# Schematic.net
KiCad netlist of a schematic drawn in EAGLE
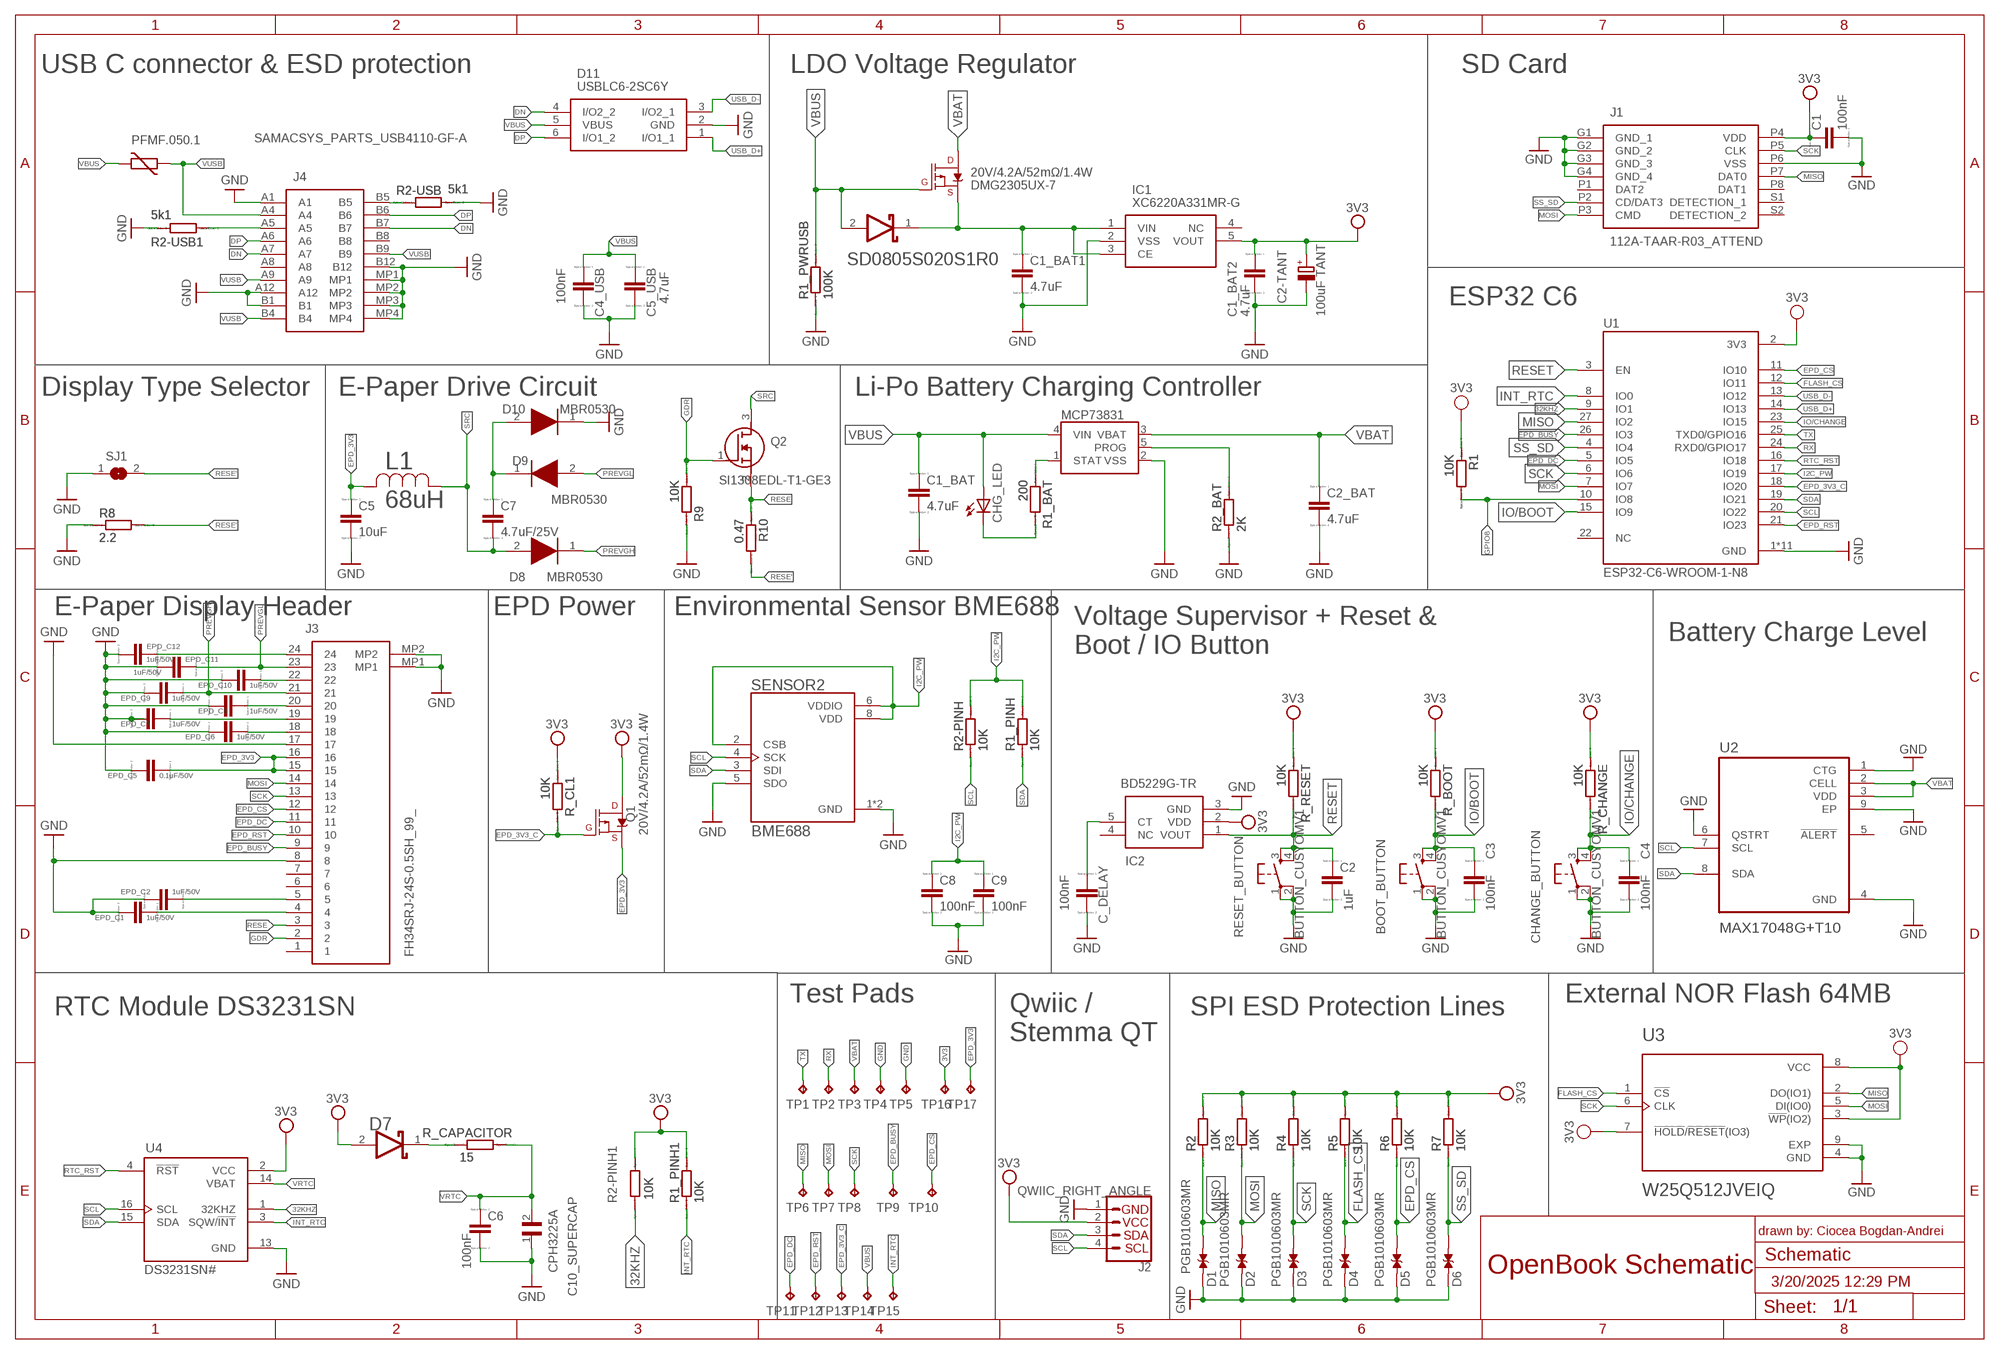
[diagram p0: schematic, sheet 1]

(export (version "E")
  (design (tool "Eeschema 10.0.6"))
  (components
    (comp (ref "BOOT_BUTTON")
      (value "BUTTON_CUSYOMV1")
      (footprint "eagle-import:MYBUTTON")
      (libsource (lib "eagle-import") (part "BUTTON_CUSYOMV1"))
    )
    (comp (ref "C1")
      (value "100nF")
      (footprint "eagle-import:EAGLE-LTSPICE_C0402")
      (libsource (lib "eagle-import") (part "EAGLE-LTSPICE_CC0402"))
    )
    (comp (ref "C1_BAT")
      (value "4.7uF")
      (footprint "eagle-import:EAGLE-LTSPICE_C0402")
      (libsource (lib "eagle-import") (part "EAGLE-LTSPICE_CC0402"))
    )
    (comp (ref "C1_BAT1")
      (value "4.7uF")
      (footprint "eagle-import:EAGLE-LTSPICE_C0402")
      (libsource (lib "eagle-import") (part "EAGLE-LTSPICE_CC0402"))
    )
    (comp (ref "C1_BAT2")
      (value "4.7uF")
      (footprint "eagle-import:EAGLE-LTSPICE_C0402")
      (libsource (lib "eagle-import") (part "EAGLE-LTSPICE_CC0402"))
    )
    (comp (ref "C2")
      (value "1uF")
      (footprint "eagle-import:EAGLE-LTSPICE_C0402")
      (libsource (lib "eagle-import") (part "EAGLE-LTSPICE_CC0402"))
    )
    (comp (ref "C2-TANT")
      (value "100uF TANT")
      (footprint "eagle-import:RCL_CT3528")
      (libsource (lib "eagle-import") (part "RCL_CPOL-EUCT3528"))
    )
    (comp (ref "C2_BAT")
      (value "4.7uF")
      (footprint "eagle-import:EAGLE-LTSPICE_C0402")
      (libsource (lib "eagle-import") (part "EAGLE-LTSPICE_CC0402"))
    )
    (comp (ref "C3")
      (value "100nF")
      (footprint "eagle-import:EAGLE-LTSPICE_C0402")
      (libsource (lib "eagle-import") (part "EAGLE-LTSPICE_CC0402"))
    )
    (comp (ref "C4")
      (value "100nF")
      (footprint "eagle-import:EAGLE-LTSPICE_C0402")
      (libsource (lib "eagle-import") (part "EAGLE-LTSPICE_CC0402"))
    )
    (comp (ref "C4_USB")
      (value "100nF")
      (footprint "eagle-import:EAGLE-LTSPICE_C0402")
      (libsource (lib "eagle-import") (part "EAGLE-LTSPICE_CC0402"))
    )
    (comp (ref "C5")
      (value "10uF")
      (footprint "eagle-import:EAGLE-LTSPICE_C0402")
      (libsource (lib "eagle-import") (part "EAGLE-LTSPICE_CC0402"))
    )
    (comp (ref "C5_USB")
      (value "4.7uF")
      (footprint "eagle-import:EAGLE-LTSPICE_C0402")
      (libsource (lib "eagle-import") (part "EAGLE-LTSPICE_CC0402"))
    )
    (comp (ref "C6")
      (value "100nF")
      (footprint "eagle-import:EAGLE-LTSPICE_C0402")
      (libsource (lib "eagle-import") (part "EAGLE-LTSPICE_CC0402"))
    )
    (comp (ref "C7")
      (value "4.7uF/25V")
      (footprint "eagle-import:EAGLE-LTSPICE_C0402")
      (libsource (lib "eagle-import") (part "EAGLE-LTSPICE_CC0402"))
    )
    (comp (ref "C8")
      (value "100nF")
      (footprint "eagle-import:EAGLE-LTSPICE_C0402")
      (libsource (lib "eagle-import") (part "EAGLE-LTSPICE_CC0402"))
    )
    (comp (ref "C9")
      (value "100nF")
      (footprint "eagle-import:EAGLE-LTSPICE_C0402")
      (libsource (lib "eagle-import") (part "EAGLE-LTSPICE_CC0402"))
    )
    (comp (ref "C10_SUPERCAP")
      (value "CPH3225A")
      (footprint "eagle-import:CAPCP3225X100N")
      (fields (field (name "MF") "Seiko Instruments"))
      (libsource (lib "eagle-import") (part "CPH3225A"))
    )
    (comp (ref "CHANGE_BUTTON")
      (value "BUTTON_CUSYOMV1")
      (footprint "eagle-import:MYBUTTON")
      (libsource (lib "eagle-import") (part "BUTTON_CUSYOMV1"))
    )
    (comp (ref "CHG_LED")
      (value "ADAFRUIT_LEDCHIP-LED0603")
      (footprint "eagle-import:ADAFRUIT_CHIP-LED0603")
      (libsource (lib "eagle-import") (part "ADAFRUIT_LEDCHIP-LED0603"))
    )
    (comp (ref "C_DELAY")
      (value "100nF")
      (footprint "eagle-import:EAGLE-LTSPICE_C0402")
      (libsource (lib "eagle-import") (part "EAGLE-LTSPICE_CC0402"))
    )
    (comp (ref "D1")
      (value "PGB1010603MR")
      (footprint "eagle-import:DIOC1608X36N")
      (fields (field (name "MF") "Littelfuse Inc."))
      (libsource (lib "eagle-import") (part "PGB1010603MR"))
    )
    (comp (ref "D2")
      (value "PGB1010603MR")
      (footprint "eagle-import:DIOC1608X36N")
      (fields (field (name "MF") "Littelfuse Inc."))
      (libsource (lib "eagle-import") (part "PGB1010603MR"))
    )
    (comp (ref "D3")
      (value "PGB1010603MR")
      (footprint "eagle-import:DIOC1608X36N")
      (fields (field (name "MF") "Littelfuse Inc."))
      (libsource (lib "eagle-import") (part "PGB1010603MR"))
    )
    (comp (ref "D4")
      (value "PGB1010603MR")
      (footprint "eagle-import:DIOC1608X36N")
      (fields (field (name "MF") "Littelfuse Inc."))
      (libsource (lib "eagle-import") (part "PGB1010603MR"))
    )
    (comp (ref "D5")
      (value "PGB1010603MR")
      (footprint "eagle-import:DIOC1608X36N")
      (fields (field (name "MF") "Littelfuse Inc."))
      (libsource (lib "eagle-import") (part "PGB1010603MR"))
    )
    (comp (ref "D6")
      (value "PGB1010603MR")
      (footprint "eagle-import:DIOC1608X36N")
      (fields (field (name "MF") "Littelfuse Inc."))
      (libsource (lib "eagle-import") (part "PGB1010603MR"))
    )
    (comp (ref "D7")
      (value "SD0805S020S1R0")
      (footprint "eagle-import:ESP32_WROVER_AVX---SD0805S020S1R0_AVX_SD0805S020S1R0_0")
      (fields
        (field (name "DIGIKEY_PART_NUMBER") "478-7800-1-ND")
        (field (name "MF") "AVX")
        (field (name "MOUSER_PART_NUMBER") "581-SD0805S020S1R0")
      )
      (libsource (lib "eagle-import") (part "ESP32_WROVER_AVX---SD0805S020S1R0_AVX_SD0805S020S1R0_0_0AVX_SD0805S020S1R0_0_0"))
    )
    (comp (ref "D8")
      (value "MBR0530")
      (footprint "eagle-import:SOD3716X135N")
      (fields (field (name "MF") "ON Semiconductor"))
      (libsource (lib "eagle-import") (part "MBR0530"))
    )
    (comp (ref "D9")
      (value "MBR0530")
      (footprint "eagle-import:SOD3716X135N")
      (fields (field (name "MF") "ON Semiconductor"))
      (libsource (lib "eagle-import") (part "MBR0530"))
    )
    (comp (ref "D10")
      (value "MBR0530")
      (footprint "eagle-import:SOD3716X135N")
      (fields (field (name "MF") "ON Semiconductor"))
      (libsource (lib "eagle-import") (part "MBR0530"))
    )
    (comp (ref "D11")
      (value "USBLC6-2SC6Y")
      (footprint "eagle-import:SOT95P280X145-6N")
      (fields (field (name "MF") "STMicroelectronics"))
      (libsource (lib "eagle-import") (part "USBLC6-2SC6Y"))
    )
    (comp (ref "DMG2305UX-7")
      (value "20V/4.2A/52mΩ/1.4W")
      (footprint "eagle-import:ESP32_WROVER_SPARKFUN-DISCRETESEMI_SOT23-3")
      (libsource (lib "eagle-import") (part "ESP32_WROVER_SPARKFUN-DISCRETESEMI_MOSFET_PCH-DMG2305UX-7"))
    )
    (comp (ref "EPD_C1")
      (value "1uF/50V")
      (footprint "eagle-import:EAGLE-LTSPICE_C0402")
      (libsource (lib "eagle-import") (part "EAGLE-LTSPICE_CC0402"))
    )
    (comp (ref "EPD_C2")
      (value "1uF/50V")
      (footprint "eagle-import:EAGLE-LTSPICE_C0402")
      (libsource (lib "eagle-import") (part "EAGLE-LTSPICE_CC0402"))
    )
    (comp (ref "EPD_C5")
      (value "0.1uF/50V")
      (footprint "eagle-import:EAGLE-LTSPICE_C0402")
      (libsource (lib "eagle-import") (part "EAGLE-LTSPICE_CC0402"))
    )
    (comp (ref "EPD_C6")
      (value "1uF/50V")
      (footprint "eagle-import:EAGLE-LTSPICE_C0402")
      (libsource (lib "eagle-import") (part "EAGLE-LTSPICE_CC0402"))
    )
    (comp (ref "EPD_C7")
      (value "1uF/50V")
      (footprint "eagle-import:EAGLE-LTSPICE_C0402")
      (libsource (lib "eagle-import") (part "EAGLE-LTSPICE_CC0402"))
    )
    (comp (ref "EPD_C8")
      (value "1uF/50V")
      (footprint "eagle-import:EAGLE-LTSPICE_C0402")
      (libsource (lib "eagle-import") (part "EAGLE-LTSPICE_CC0402"))
    )
    (comp (ref "EPD_C9")
      (value "1uF/50V")
      (footprint "eagle-import:EAGLE-LTSPICE_C0402")
      (libsource (lib "eagle-import") (part "EAGLE-LTSPICE_CC0402"))
    )
    (comp (ref "EPD_C10")
      (value "1uF/50V")
      (footprint "eagle-import:EAGLE-LTSPICE_C0402")
      (libsource (lib "eagle-import") (part "EAGLE-LTSPICE_CC0402"))
    )
    (comp (ref "EPD_C11")
      (value "1uF/50V")
      (footprint "eagle-import:EAGLE-LTSPICE_C0402")
      (libsource (lib "eagle-import") (part "EAGLE-LTSPICE_CC0402"))
    )
    (comp (ref "EPD_C12")
      (value "1uF/50V")
      (footprint "eagle-import:EAGLE-LTSPICE_C0402")
      (libsource (lib "eagle-import") (part "EAGLE-LTSPICE_CC0402"))
    )
    (comp (ref "IC1")
      (value "XC6220A331MR-G")
      (footprint "eagle-import:SOT95P280X120-5N")
      (fields (field (name "MOUSER_PART_NUMBER") "865-XC6220A331MR-G"))
      (libsource (lib "eagle-import") (part "XC6220A331MR-G"))
    )
    (comp (ref "IC2")
      (value "BD5229G-TR")
      (footprint "eagle-import:SOT95P280X125-5N")
      (fields (field (name "MOUSER_PART_NUMBER") "755-BD5229G-TR"))
      (libsource (lib "eagle-import") (part "BD5229G-TR"))
    )
    (comp (ref "J1")
      (value "112A-TAAR-R03_ATTEND")
      (footprint "eagle-import:112ATAARR03ATTEND")
      (fields (field (name "MANUFACTURER_PART_NUMBER") "112A-TAAR-R03 ATTEND"))
      (libsource (lib "eagle-import") (part "112A-TAAR-R03_ATTEND"))
    )
    (comp (ref "J2")
      (value "QWIIC_RIGHT_ANGLE")
      (footprint "eagle-import:JST04_1MM_RA")
      (libsource (lib "eagle-import") (part "QWIIC_CONNECTORJS-1MM"))
    )
    (comp (ref "J3")
      (value "FH34SRJ-24S-0.5SH_99_")
      (footprint "eagle-import:FH34SRJ24S05SH99")
      (fields
        (field (name "MANUFACTURER_PART_NUMBER") "FH34SRJ-24S-0.5SH(99)")
        (field (name "MOUSER_PART_NUMBER") "798-FH34SRJ24S05SH99")
      )
      (libsource (lib "eagle-import") (part "FH34SRJ-24S-0.5SH_99_"))
    )
    (comp (ref "J4")
      (value "SAMACSYS_PARTS_USB4110-GF-A")
      (footprint "eagle-import:SAMACSYS_PARTS_USB4110GFA")
      (fields
        (field (name "MANUFACTURER_PART_NUMBER") "USB4110-GF-A")
        (field (name "MOUSER_PART_NUMBER") "640-USB4110-GF-A")
      )
      (libsource (lib "eagle-import") (part "SAMACSYS_PARTS_USB4110-GF-A"))
    )
    (comp (ref "L1")
      (value "68uH")
      (footprint "eagle-import:IND_4828-WE-TPC_WRE")
      (fields
        (field (name "MANUFACTURER_PART_NUMBER") "744043680")
        (field (name "COPYRIGHT") "Copyright (C) 2024 Ultra Librarian. All rights reserved.")
      )
      (libsource (lib "eagle-import") (part "744043680IND_4828-WE-TPC_WRE"))
    )
    (comp (ref "MCP73831")
      (value "ESP32_WROVER_SPARKFUN-IC-POWER_MCP73831")
      (footprint "eagle-import:ESP32_WROVER_SPARKFUN-IC-POWER_SOT23-5")
      (libsource (lib "eagle-import") (part "ESP32_WROVER_SPARKFUN-IC-POWER_MCP73831"))
    )
    (comp (ref "PFMF.050.1")
      (value "ESP32C6_VARISTORCN1812")
      (footprint "eagle-import:ESP32C6_VARISTOR_CT_CN1812")
      (libsource (lib "eagle-import") (part "ESP32C6_VARISTORCN1812"))
    )
    (comp (ref "Q1")
      (value "20V/4.2A/52mΩ/1.4W")
      (footprint "eagle-import:ESP32_WROVER_SPARKFUN-DISCRETESEMI_SOT23-3")
      (libsource (lib "eagle-import") (part "ESP32_WROVER_SPARKFUN-DISCRETESEMI_MOSFET_PCH-DMG2305UX-7"))
    )
    (comp (ref "Q2")
      (value "SI1308EDL-T1-GE3")
      (footprint "eagle-import:SOT65P210X110-3N")
      (fields (field (name "MF") "Vishay Siliconix"))
      (libsource (lib "eagle-import") (part "SI1308EDL-T1-GE3"))
    )
    (comp (ref "R1")
      (value "10K")
      (footprint "eagle-import:ESP32_WROVER_EAGLE-LTSPICE_R0402")
      (libsource (lib "eagle-import") (part "ESP32_WROVER_EAGLE-LTSPICE_RR0402"))
    )
    (comp (ref "R1_BAT")
      (value "200")
      (footprint "eagle-import:ESP32_WROVER_EAGLE-LTSPICE_R0402")
      (libsource (lib "eagle-import") (part "ESP32_WROVER_EAGLE-LTSPICE_RR0402"))
    )
    (comp (ref "R1_PINH")
      (value "10K")
      (footprint "eagle-import:ESP32_WROVER_EAGLE-LTSPICE_R0402")
      (libsource (lib "eagle-import") (part "ESP32_WROVER_EAGLE-LTSPICE_RR0402"))
    )
    (comp (ref "R1_PINH1")
      (value "10K")
      (footprint "eagle-import:ESP32_WROVER_EAGLE-LTSPICE_R0402")
      (libsource (lib "eagle-import") (part "ESP32_WROVER_EAGLE-LTSPICE_RR0402"))
    )
    (comp (ref "R1_PWRUSB")
      (value "100K")
      (footprint "eagle-import:ESP32_WROVER_EAGLE-LTSPICE_R0402")
      (libsource (lib "eagle-import") (part "ESP32_WROVER_EAGLE-LTSPICE_RR0402"))
    )
    (comp (ref "R2")
      (value "10K")
      (footprint "eagle-import:ESP32_WROVER_EAGLE-LTSPICE_R0402")
      (libsource (lib "eagle-import") (part "ESP32_WROVER_EAGLE-LTSPICE_RR0402"))
    )
    (comp (ref "R2-PINH")
      (value "10K")
      (footprint "eagle-import:ESP32_WROVER_EAGLE-LTSPICE_R0402")
      (libsource (lib "eagle-import") (part "ESP32_WROVER_EAGLE-LTSPICE_RR0402"))
    )
    (comp (ref "R2-PINH1")
      (value "10K")
      (footprint "eagle-import:ESP32_WROVER_EAGLE-LTSPICE_R0402")
      (libsource (lib "eagle-import") (part "ESP32_WROVER_EAGLE-LTSPICE_RR0402"))
    )
    (comp (ref "R2-USB")
      (value "5k1")
      (footprint "eagle-import:ESP32_WROVER_EAGLE-LTSPICE_R0402")
      (libsource (lib "eagle-import") (part "ESP32_WROVER_EAGLE-LTSPICE_RR0402"))
    )
    (comp (ref "R2-USB1")
      (value "5k1")
      (footprint "eagle-import:ESP32_WROVER_EAGLE-LTSPICE_R0402")
      (libsource (lib "eagle-import") (part "ESP32_WROVER_EAGLE-LTSPICE_RR0402"))
    )
    (comp (ref "R2_BAT")
      (value "2K")
      (footprint "eagle-import:ESP32_WROVER_EAGLE-LTSPICE_R0402")
      (libsource (lib "eagle-import") (part "ESP32_WROVER_EAGLE-LTSPICE_RR0402"))
    )
    (comp (ref "R3")
      (value "10K")
      (footprint "eagle-import:ESP32_WROVER_EAGLE-LTSPICE_R0402")
      (libsource (lib "eagle-import") (part "ESP32_WROVER_EAGLE-LTSPICE_RR0402"))
    )
    (comp (ref "R4")
      (value "10K")
      (footprint "eagle-import:ESP32_WROVER_EAGLE-LTSPICE_R0402")
      (libsource (lib "eagle-import") (part "ESP32_WROVER_EAGLE-LTSPICE_RR0402"))
    )
    (comp (ref "R5")
      (value "10K")
      (footprint "eagle-import:ESP32_WROVER_EAGLE-LTSPICE_R0402")
      (libsource (lib "eagle-import") (part "ESP32_WROVER_EAGLE-LTSPICE_RR0402"))
    )
    (comp (ref "R6")
      (value "10K")
      (footprint "eagle-import:ESP32_WROVER_EAGLE-LTSPICE_R0402")
      (libsource (lib "eagle-import") (part "ESP32_WROVER_EAGLE-LTSPICE_RR0402"))
    )
    (comp (ref "R7")
      (value "10K")
      (footprint "eagle-import:ESP32_WROVER_EAGLE-LTSPICE_R0402")
      (libsource (lib "eagle-import") (part "ESP32_WROVER_EAGLE-LTSPICE_RR0402"))
    )
    (comp (ref "R8")
      (value "2.2")
      (footprint "eagle-import:ESP32_WROVER_EAGLE-LTSPICE_R0402")
      (libsource (lib "eagle-import") (part "ESP32_WROVER_EAGLE-LTSPICE_RR0402"))
    )
    (comp (ref "R9")
      (value "10K")
      (footprint "eagle-import:ESP32_WROVER_EAGLE-LTSPICE_R0402")
      (libsource (lib "eagle-import") (part "ESP32_WROVER_EAGLE-LTSPICE_RR0402"))
    )
    (comp (ref "R10")
      (value "0.47")
      (footprint "eagle-import:ESP32_WROVER_EAGLE-LTSPICE_R0402")
      (libsource (lib "eagle-import") (part "ESP32_WROVER_EAGLE-LTSPICE_RR0402"))
    )
    (comp (ref "RESET_BUTTON")
      (value "BUTTON_CUSYOMV1")
      (footprint "eagle-import:MYBUTTON")
      (libsource (lib "eagle-import") (part "BUTTON_CUSYOMV1"))
    )
    (comp (ref "R_BOOT")
      (value "10K")
      (footprint "eagle-import:ESP32_WROVER_EAGLE-LTSPICE_R0402")
      (libsource (lib "eagle-import") (part "ESP32_WROVER_EAGLE-LTSPICE_RR0402"))
    )
    (comp (ref "R_CAPACITOR")
      (value "15")
      (footprint "eagle-import:ESP32_WROVER_EAGLE-LTSPICE_R0402")
      (libsource (lib "eagle-import") (part "ESP32_WROVER_EAGLE-LTSPICE_RR0402"))
    )
    (comp (ref "R_CHANGE")
      (value "10K")
      (footprint "eagle-import:ESP32_WROVER_EAGLE-LTSPICE_R0402")
      (libsource (lib "eagle-import") (part "ESP32_WROVER_EAGLE-LTSPICE_RR0402"))
    )
    (comp (ref "R_CL1")
      (value "10K")
      (footprint "eagle-import:ESP32_WROVER_EAGLE-LTSPICE_R0402")
      (libsource (lib "eagle-import") (part "ESP32_WROVER_EAGLE-LTSPICE_RR0402"))
    )
    (comp (ref "R_RESET")
      (value "10K")
      (footprint "eagle-import:ESP32_WROVER_EAGLE-LTSPICE_R0402")
      (libsource (lib "eagle-import") (part "ESP32_WROVER_EAGLE-LTSPICE_RR0402"))
    )
    (comp (ref "SD0805S020S1R0")
      (value "ESP32_WROVER_AVX---SD0805S020S1R0_AVX_SD0805S020S1R0_0_0AVX_SD0805S020S1R0_0_0")
      (footprint "eagle-import:ESP32_WROVER_AVX---SD0805S020S1R0_AVX_SD0805S020S1R0_0")
      (fields
        (field (name "DIGIKEY_PART_NUMBER") "478-7800-1-ND")
        (field (name "MF") "AVX")
        (field (name "MOUSER_PART_NUMBER") "581-SD0805S020S1R0")
      )
      (libsource (lib "eagle-import") (part "ESP32_WROVER_AVX---SD0805S020S1R0_AVX_SD0805S020S1R0_0_0AVX_SD0805S020S1R0_0_0"))
    )
    (comp (ref "SENSOR2")
      (value "BME688")
      (footprint "eagle-import:ESP32_WROVER_BME680_PSON80P300X300X100-8N")
      (fields (field (name "MF") "Bosch Sensortec") (field (name "MP") "BME680"))
      (libsource (lib "eagle-import") (part "ESP32_WROVER_BME680_BME680"))
    )
    (comp (ref "SJ1") (value "SJ") (footprint "eagle-import:SJ") (libsource (lib "eagle-import") (part "SJ")))
    (comp (ref "TP1")
      (value "TX")
      (footprint "eagle-import:TP20R")
      (libsource (lib "eagle-import") (part "TPTP20R"))
    )
    (comp (ref "TP2")
      (value "RX")
      (footprint "eagle-import:TP20R")
      (libsource (lib "eagle-import") (part "TPTP20R"))
    )
    (comp (ref "TP3")
      (value "VBAT")
      (footprint "eagle-import:TP20R")
      (libsource (lib "eagle-import") (part "TPTP20R"))
    )
    (comp (ref "TP4")
      (value "GND")
      (footprint "eagle-import:TP20R")
      (libsource (lib "eagle-import") (part "TPTP20R"))
    )
    (comp (ref "TP5")
      (value "GND")
      (footprint "eagle-import:TP20R")
      (libsource (lib "eagle-import") (part "TPTP20R"))
    )
    (comp (ref "TP6")
      (value "MISO")
      (footprint "eagle-import:TP20R")
      (libsource (lib "eagle-import") (part "TPTP20R"))
    )
    (comp (ref "TP7")
      (value "MOSI")
      (footprint "eagle-import:TP20R")
      (libsource (lib "eagle-import") (part "TPTP20R"))
    )
    (comp (ref "TP8")
      (value "SCK")
      (footprint "eagle-import:TP20R")
      (libsource (lib "eagle-import") (part "TPTP20R"))
    )
    (comp (ref "TP9")
      (value "EPD_BUSY")
      (footprint "eagle-import:TP20R")
      (libsource (lib "eagle-import") (part "TPTP20R"))
    )
    (comp (ref "TP10")
      (value "EPD_CS")
      (footprint "eagle-import:TP20R")
      (libsource (lib "eagle-import") (part "TPTP20R"))
    )
    (comp (ref "TP11")
      (value "EPD_DC")
      (footprint "eagle-import:TP20R")
      (libsource (lib "eagle-import") (part "TPTP20R"))
    )
    (comp (ref "TP12")
      (value "EPD_RST")
      (footprint "eagle-import:TP20R")
      (libsource (lib "eagle-import") (part "TPTP20R"))
    )
    (comp (ref "TP13")
      (value "EPD_3V3_C")
      (footprint "eagle-import:TP20R")
      (libsource (lib "eagle-import") (part "TPTP20R"))
    )
    (comp (ref "TP14")
      (value "VBUS")
      (footprint "eagle-import:TP20R")
      (libsource (lib "eagle-import") (part "TPTP20R"))
    )
    (comp (ref "TP15")
      (value "INT_RTC")
      (footprint "eagle-import:TP20R")
      (libsource (lib "eagle-import") (part "TPTP20R"))
    )
    (comp (ref "TP16")
      (value "3V3")
      (footprint "eagle-import:TP20R")
      (libsource (lib "eagle-import") (part "TPTP20R"))
    )
    (comp (ref "TP17")
      (value "EPD_3V3")
      (footprint "eagle-import:TP20R")
      (libsource (lib "eagle-import") (part "TPTP20R"))
    )
    (comp (ref "U1")
      (value "ESP32-C6-WROOM-1-N8")
      (footprint "eagle-import:XCVR_ESP32-C6-WROOM-1-N8")
      (fields (field (name "MF") "Espressif Systems"))
      (libsource (lib "eagle-import") (part "ESP32-C6-WROOM-1-N8"))
    )
    (comp (ref "U2")
      (value "MAX17048G+T10")
      (footprint "eagle-import:SON50P200X200X80-9N")
      (fields (field (name "MF") "Analog Devices"))
      (libsource (lib "eagle-import") (part "MAX17048G+T10"))
    )
    (comp (ref "U3")
      (value "W25Q512JVEIQ")
      (footprint "eagle-import:SON127P600X800X80-9N")
      (fields (field (name "MF") "Winbond Electronics"))
      (libsource (lib "eagle-import") (part "W25Q512JVEIQ"))
    )
    (comp (ref "U4")
      (value "DS3231SN#")
      (footprint "eagle-import:SOIC127P1032X265-16N")
      (fields (field (name "MF") "Analog Devices"))
      (libsource (lib "eagle-import") (part "DS3231SN#"))
    )
  )
  (nets
    (net (code "1") (name "3V3") (class "Default")
      (node (ref "C1") (pin "1") (pinfunction "1_1") (pintype "passive"))
      (node (ref "C1_BAT2") (pin "1") (pinfunction "1_1") (pintype "passive"))
      (node (ref "C2-TANT") (pin "+") (pinfunction "+_+") (pintype "passive"))
      (node (ref "D7") (pin "2") (pinfunction "ANODE_2") (pintype "bidirectional"))
      (node (ref "IC1") (pin "5") (pinfunction "VOUT_5") (pintype "bidirectional"))
      (node (ref "IC2") (pin "2") (pinfunction "VDD_2") (pintype "bidirectional"))
      (node (ref "J1") (pin "P4") (pinfunction "VDD_P4") (pintype "bidirectional"))
      (node (ref "J2") (pin "2") (pinfunction "2_2") (pintype "power_in"))
      (node (ref "Q1") (pin "3") (pinfunction "D_3") (pintype "bidirectional"))
      (node (ref "R1") (pin "1") (pinfunction "1_1") (pintype "passive"))
      (node (ref "R1_PINH1") (pin "2") (pinfunction "2_2") (pintype "passive"))
      (node (ref "R2") (pin "2") (pinfunction "2_2") (pintype "passive"))
      (node (ref "R2-PINH1") (pin "1") (pinfunction "1_1") (pintype "passive"))
      (node (ref "R3") (pin "2") (pinfunction "2_2") (pintype "passive"))
      (node (ref "R4") (pin "2") (pinfunction "2_2") (pintype "passive"))
      (node (ref "R5") (pin "2") (pinfunction "2_2") (pintype "passive"))
      (node (ref "R6") (pin "2") (pinfunction "2_2") (pintype "passive"))
      (node (ref "R7") (pin "2") (pinfunction "2_2") (pintype "passive"))
      (node (ref "R_BOOT") (pin "1") (pinfunction "1_1") (pintype "passive"))
      (node (ref "R_CHANGE") (pin "1") (pinfunction "1_1") (pintype "passive"))
      (node (ref "R_CL1") (pin "1") (pinfunction "1_1") (pintype "passive"))
      (node (ref "R_RESET") (pin "1") (pinfunction "1_1") (pintype "passive"))
      (node (ref "TP16") (pin "TP") (pinfunction "TP_TP") (pintype "input"))
      (node (ref "U1") (pin "2") (pinfunction "3V3_2") (pintype "power_in"))
      (node (ref "U3") (pin "3") (pinfunction "~{WP}(IO2)_3") (pintype "bidirectional"))
      (node (ref "U3") (pin "7") (pinfunction "~{HOLD}/~{RESET}(IO3)_7") (pintype "bidirectional"))
      (node (ref "U3") (pin "8") (pinfunction "VCC_8") (pintype "power_in"))
      (node (ref "U4") (pin "2") (pinfunction "VCC_2") (pintype "power_in"))
    )
    (net (code "2") (name "32KHZ") (class "Default")
      (node (ref "R2-PINH1") (pin "2") (pinfunction "2_2") (pintype "passive"))
      (node (ref "U1") (pin "9") (pinfunction "IO1_9") (pintype "bidirectional"))
      (node (ref "U4") (pin "1") (pinfunction "32KHZ_1") (pintype "output"))
    )
    (net (code "3") (name "DN") (class "Default")
      (node (ref "D11") (pin "4") (pinfunction "I/O2_2_4") (pintype "bidirectional"))
      (node (ref "J4") (pin "A7") (pinfunction "A7_A7") (pintype "bidirectional"))
      (node (ref "J4") (pin "B7") (pinfunction "B7_B7") (pintype "bidirectional"))
    )
    (net (code "4") (name "DP") (class "Default")
      (node (ref "D11") (pin "6") (pinfunction "I/O1_2_6") (pintype "bidirectional"))
      (node (ref "J4") (pin "A6") (pinfunction "A6_A6") (pintype "bidirectional"))
      (node (ref "J4") (pin "B6") (pinfunction "B6_B6") (pintype "bidirectional"))
    )
    (net (code "5") (name "EPD_3V3") (class "Default")
      (node (ref "C5") (pin "1") (pinfunction "1_1") (pintype "passive"))
      (node (ref "EPD_C5") (pin "1") (pinfunction "1_1") (pintype "passive"))
      (node (ref "J3") (pin "15") (pinfunction "15_15") (pintype "bidirectional"))
      (node (ref "J3") (pin "16") (pinfunction "16_16") (pintype "bidirectional"))
      (node (ref "L1") (pin "2") (pinfunction "2_2") (pintype "passive"))
      (node (ref "Q1") (pin "2") (pinfunction "S_2") (pintype "bidirectional"))
      (node (ref "TP17") (pin "TP") (pinfunction "TP_TP") (pintype "input"))
    )
    (net (code "6") (name "EPD_3V3_C") (class "Default")
      (node (ref "Q1") (pin "1") (pinfunction "G_1") (pintype "bidirectional"))
      (node (ref "R_CL1") (pin "2") (pinfunction "2_2") (pintype "passive"))
      (node (ref "TP13") (pin "TP") (pinfunction "TP_TP") (pintype "input"))
      (node (ref "U1") (pin "18") (pinfunction "IO20_18") (pintype "bidirectional"))
    )
    (net (code "7") (name "EPD_BUSY") (class "Default")
      (node (ref "J3") (pin "9") (pinfunction "9_9") (pintype "bidirectional"))
      (node (ref "TP9") (pin "TP") (pinfunction "TP_TP") (pintype "input"))
      (node (ref "U1") (pin "26") (pinfunction "IO3_26") (pintype "bidirectional"))
    )
    (net (code "8") (name "EPD_CS") (class "Default")
      (node (ref "D5") (pin "2") (pinfunction "2_2") (pintype "passive"))
      (node (ref "J3") (pin "12") (pinfunction "12_12") (pintype "bidirectional"))
      (node (ref "R6") (pin "1") (pinfunction "1_1") (pintype "passive"))
      (node (ref "TP10") (pin "TP") (pinfunction "TP_TP") (pintype "input"))
      (node (ref "U1") (pin "11") (pinfunction "IO10_11") (pintype "bidirectional"))
    )
    (net (code "9") (name "EPD_DC") (class "Default")
      (node (ref "J3") (pin "11") (pinfunction "11_11") (pintype "bidirectional"))
      (node (ref "TP11") (pin "TP") (pinfunction "TP_TP") (pintype "input"))
      (node (ref "U1") (pin "5") (pinfunction "IO5_5") (pintype "bidirectional"))
    )
    (net (code "10") (name "EPD_RST") (class "Default")
      (node (ref "J3") (pin "10") (pinfunction "10_10") (pintype "bidirectional"))
      (node (ref "TP12") (pin "TP") (pinfunction "TP_TP") (pintype "input"))
      (node (ref "U1") (pin "21") (pinfunction "IO23_21") (pintype "bidirectional"))
    )
    (net (code "11") (name "FLASH_CS") (class "Default")
      (node (ref "D4") (pin "2") (pinfunction "2_2") (pintype "passive"))
      (node (ref "R5") (pin "1") (pinfunction "1_1") (pintype "passive"))
      (node (ref "U1") (pin "12") (pinfunction "IO11_12") (pintype "bidirectional"))
      (node (ref "U3") (pin "1") (pinfunction "~{CS}_1") (pintype "input"))
    )
    (net (code "12") (name "GDR") (class "Default")
      (node (ref "J3") (pin "2") (pinfunction "2_2") (pintype "bidirectional"))
      (node (ref "Q2") (pin "1") (pinfunction "G_1") (pintype "bidirectional"))
      (node (ref "R9") (pin "1") (pinfunction "1_1") (pintype "passive"))
    )
    (net (code "13") (name "GND") (class "Default")
      (node (ref "BOOT_BUTTON") (pin "1") (pinfunction "1_1") (pintype "passive"))
      (node (ref "BOOT_BUTTON") (pin "2") (pinfunction "2_2") (pintype "passive"))
      (node (ref "C1") (pin "2") (pinfunction "2_2") (pintype "passive"))
      (node (ref "C10_SUPERCAP") (pin "1") (pinfunction "1_1") (pintype "passive"))
      (node (ref "C1_BAT") (pin "2") (pinfunction "2_2") (pintype "passive"))
      (node (ref "C1_BAT1") (pin "2") (pinfunction "2_2") (pintype "passive"))
      (node (ref "C1_BAT2") (pin "2") (pinfunction "2_2") (pintype "passive"))
      (node (ref "C2") (pin "2") (pinfunction "2_2") (pintype "passive"))
      (node (ref "C2-TANT") (pin "-") (pinfunction "-_-") (pintype "passive"))
      (node (ref "C2_BAT") (pin "2") (pinfunction "2_2") (pintype "passive"))
      (node (ref "C3") (pin "2") (pinfunction "2_2") (pintype "passive"))
      (node (ref "C4") (pin "2") (pinfunction "2_2") (pintype "passive"))
      (node (ref "C4_USB") (pin "2") (pinfunction "2_2") (pintype "passive"))
      (node (ref "C5") (pin "2") (pinfunction "2_2") (pintype "passive"))
      (node (ref "C5_USB") (pin "2") (pinfunction "2_2") (pintype "passive"))
      (node (ref "C6") (pin "2") (pinfunction "2_2") (pintype "passive"))
      (node (ref "C8") (pin "2") (pinfunction "2_2") (pintype "passive"))
      (node (ref "C9") (pin "2") (pinfunction "2_2") (pintype "passive"))
      (node (ref "CHANGE_BUTTON") (pin "1") (pinfunction "1_1") (pintype "passive"))
      (node (ref "CHANGE_BUTTON") (pin "2") (pinfunction "2_2") (pintype "passive"))
      (node (ref "C_DELAY") (pin "2") (pinfunction "2_2") (pintype "passive"))
      (node (ref "D1") (pin "1") (pinfunction "1_1") (pintype "passive"))
      (node (ref "D10") (pin "1") (pinfunction "K_1") (pintype "bidirectional"))
      (node (ref "D11") (pin "2") (pinfunction "GND_2") (pintype "bidirectional"))
      (node (ref "D2") (pin "1") (pinfunction "1_1") (pintype "passive"))
      (node (ref "D3") (pin "1") (pinfunction "1_1") (pintype "passive"))
      (node (ref "D4") (pin "1") (pinfunction "1_1") (pintype "passive"))
      (node (ref "D5") (pin "1") (pinfunction "1_1") (pintype "passive"))
      (node (ref "D6") (pin "1") (pinfunction "1_1") (pintype "passive"))
      (node (ref "EPD_C1") (pin "2") (pinfunction "2_2") (pintype "passive"))
      (node (ref "EPD_C10") (pin "2") (pinfunction "2_2") (pintype "passive"))
      (node (ref "EPD_C11") (pin "2") (pinfunction "2_2") (pintype "passive"))
      (node (ref "EPD_C12") (pin "2") (pinfunction "2_2") (pintype "passive"))
      (node (ref "EPD_C2") (pin "2") (pinfunction "2_2") (pintype "passive"))
      (node (ref "EPD_C5") (pin "2") (pinfunction "2_2") (pintype "passive"))
      (node (ref "EPD_C6") (pin "2") (pinfunction "2_2") (pintype "passive"))
      (node (ref "EPD_C7") (pin "2") (pinfunction "2_2") (pintype "passive"))
      (node (ref "EPD_C8") (pin "2") (pinfunction "2_2") (pintype "passive"))
      (node (ref "EPD_C9") (pin "2") (pinfunction "2_2") (pintype "passive"))
      (node (ref "IC1") (pin "2") (pinfunction "VSS_2") (pintype "bidirectional"))
      (node (ref "IC2") (pin "3") (pinfunction "GND_3") (pintype "bidirectional"))
      (node (ref "J1") (pin "G1") (pinfunction "GND_1_G1") (pintype "bidirectional"))
      (node (ref "J1") (pin "G2") (pinfunction "GND_2_G2") (pintype "bidirectional"))
      (node (ref "J1") (pin "G3") (pinfunction "GND_3_G3") (pintype "bidirectional"))
      (node (ref "J1") (pin "G4") (pinfunction "GND_4_G4") (pintype "bidirectional"))
      (node (ref "J1") (pin "P6") (pinfunction "VSS_P6") (pintype "bidirectional"))
      (node (ref "J2") (pin "1") (pinfunction "1_1") (pintype "power_in"))
      (node (ref "J3") (pin "17") (pinfunction "17_17") (pintype "bidirectional"))
      (node (ref "J3") (pin "8") (pinfunction "8_8") (pintype "bidirectional"))
      (node (ref "J3") (pin "MP1") (pinfunction "MP1_MP1") (pintype "bidirectional"))
      (node (ref "J3") (pin "MP2") (pinfunction "MP2_MP2") (pintype "bidirectional"))
      (node (ref "J4") (pin "A1") (pinfunction "A1_A1") (pintype "bidirectional"))
      (node (ref "J4") (pin "A12") (pinfunction "A12_A12") (pintype "bidirectional"))
      (node (ref "J4") (pin "B1") (pinfunction "B1_B1") (pintype "bidirectional"))
      (node (ref "J4") (pin "B12") (pinfunction "B12_B12") (pintype "bidirectional"))
      (node (ref "J4") (pin "MP1") (pinfunction "MP1_MP1") (pintype "bidirectional"))
      (node (ref "J4") (pin "MP2") (pinfunction "MP2_MP2") (pintype "bidirectional"))
      (node (ref "J4") (pin "MP3") (pinfunction "MP3_MP3") (pintype "bidirectional"))
      (node (ref "J4") (pin "MP4") (pinfunction "MP4_MP4") (pintype "bidirectional"))
      (node (ref "MCP73831") (pin "2") (pinfunction "VSS_2") (pintype "power_in"))
      (node (ref "R1_PWRUSB") (pin "1") (pinfunction "1_1") (pintype "passive"))
      (node (ref "R2-USB") (pin "2") (pinfunction "2_2") (pintype "passive"))
      (node (ref "R2-USB1") (pin "1") (pinfunction "1_1") (pintype "passive"))
      (node (ref "R2_BAT") (pin "1") (pinfunction "1_1") (pintype "passive"))
      (node (ref "R8") (pin "1") (pinfunction "1_1") (pintype "passive"))
      (node (ref "R9") (pin "2") (pinfunction "2_2") (pintype "passive"))
      (node (ref "RESET_BUTTON") (pin "1") (pinfunction "1_1") (pintype "passive"))
      (node (ref "RESET_BUTTON") (pin "2") (pinfunction "2_2") (pintype "passive"))
      (node (ref "SENSOR2") (pin "1") (pinfunction "GND_1") (pintype "power_in"))
      (node (ref "SENSOR2") (pin "5") (pinfunction "SDO_5") (pintype "bidirectional"))
      (node (ref "SENSOR2") (pin "7") (pinfunction "GND_7") (pintype "power_in"))
      (node (ref "SJ1") (pin "1") (pinfunction "1_1") (pintype "passive"))
      (node (ref "TP4") (pin "TP") (pinfunction "TP_TP") (pintype "input"))
      (node (ref "TP5") (pin "TP") (pinfunction "TP_TP") (pintype "input"))
      (node (ref "U1") (pin "1") (pinfunction "GND_1") (pintype "power_in"))
      (node (ref "U1") (pin "28") (pinfunction "GND_28") (pintype "power_in"))
      (node (ref "U1") (pin "29_1") (pinfunction "GND_29_1") (pintype "power_in"))
      (node (ref "U1") (pin "29_2") (pinfunction "GND_29_2") (pintype "power_in"))
      (node (ref "U1") (pin "29_3") (pinfunction "GND_29_3") (pintype "power_in"))
      (node (ref "U1") (pin "29_4") (pinfunction "GND_29_4") (pintype "power_in"))
      (node (ref "U1") (pin "29_5") (pinfunction "GND_29_5") (pintype "power_in"))
      (node (ref "U1") (pin "29_6") (pinfunction "GND_29_6") (pintype "power_in"))
      (node (ref "U1") (pin "29_7") (pinfunction "GND_29_7") (pintype "power_in"))
      (node (ref "U1") (pin "29_8") (pinfunction "GND_29_8") (pintype "power_in"))
      (node (ref "U1") (pin "29_9") (pinfunction "GND_29_9") (pintype "power_in"))
      (node (ref "U2") (pin "1") (pinfunction "CTG_1") (pintype "power_in"))
      (node (ref "U2") (pin "4") (pinfunction "GND_4") (pintype "power_in"))
      (node (ref "U2") (pin "6") (pinfunction "QSTRT_6") (pintype "input"))
      (node (ref "U2") (pin "9") (pinfunction "EP_9") (pintype "power_in"))
      (node (ref "U3") (pin "4") (pinfunction "GND_4") (pintype "power_in"))
      (node (ref "U3") (pin "9") (pinfunction "EXP_9") (pintype "passive"))
      (node (ref "U4") (pin "13") (pinfunction "GND_13") (pintype "power_in"))
    )
    (net (code "14") (name "GPIO8") (class "Default")
      (node (ref "R1") (pin "2") (pinfunction "2_2") (pintype "passive"))
      (node (ref "U1") (pin "10") (pinfunction "IO8_10") (pintype "bidirectional"))
    )
    (net (code "15") (name "I2C_PW") (class "Default")
      (node (ref "C8") (pin "1") (pinfunction "1_1") (pintype "passive"))
      (node (ref "C9") (pin "1") (pinfunction "1_1") (pintype "passive"))
      (node (ref "R1_PINH") (pin "2") (pinfunction "2_2") (pintype "passive"))
      (node (ref "R2-PINH") (pin "2") (pinfunction "2_2") (pintype "passive"))
      (node (ref "SENSOR2") (pin "2") (pinfunction "CSB_2") (pintype "input"))
      (node (ref "SENSOR2") (pin "6") (pinfunction "VDDIO_6") (pintype "power_in"))
      (node (ref "SENSOR2") (pin "8") (pinfunction "VDD_8") (pintype "power_in"))
      (node (ref "U1") (pin "17") (pinfunction "IO19_17") (pintype "bidirectional"))
    )
    (net (code "16") (name "INT_RTC") (class "Default")
      (node (ref "R1_PINH1") (pin "1") (pinfunction "1_1") (pintype "passive"))
      (node (ref "TP15") (pin "TP") (pinfunction "TP_TP") (pintype "input"))
      (node (ref "U1") (pin "8") (pinfunction "IO0_8") (pintype "bidirectional"))
      (node (ref "U4") (pin "3") (pinfunction "SQW/~{INT}_3") (pintype "output"))
    )
    (net (code "17") (name "IO{slash}BOOT") (class "Default")
      (node (ref "BOOT_BUTTON") (pin "3") (pinfunction "3_3") (pintype "passive"))
      (node (ref "BOOT_BUTTON") (pin "4") (pinfunction "4_4") (pintype "passive"))
      (node (ref "C3") (pin "1") (pinfunction "1_1") (pintype "passive"))
      (node (ref "R_BOOT") (pin "2") (pinfunction "2_2") (pintype "passive"))
      (node (ref "U1") (pin "15") (pinfunction "IO9_15") (pintype "bidirectional"))
    )
    (net (code "18") (name "IO{slash}CHANGE") (class "Default")
      (node (ref "C4") (pin "1") (pinfunction "1_1") (pintype "passive"))
      (node (ref "CHANGE_BUTTON") (pin "3") (pinfunction "3_3") (pintype "passive"))
      (node (ref "CHANGE_BUTTON") (pin "4") (pinfunction "4_4") (pintype "passive"))
      (node (ref "R_CHANGE") (pin "2") (pinfunction "2_2") (pintype "passive"))
      (node (ref "U1") (pin "23") (pinfunction "IO15_23") (pintype "bidirectional"))
    )
    (net (code "19") (name "MISO") (class "Default")
      (node (ref "D1") (pin "2") (pinfunction "2_2") (pintype "passive"))
      (node (ref "J1") (pin "P7") (pinfunction "DAT0_P7") (pintype "bidirectional"))
      (node (ref "R2") (pin "1") (pinfunction "1_1") (pintype "passive"))
      (node (ref "TP6") (pin "TP") (pinfunction "TP_TP") (pintype "input"))
      (node (ref "U1") (pin "27") (pinfunction "IO2_27") (pintype "bidirectional"))
      (node (ref "U3") (pin "2") (pinfunction "DO(IO1)_2") (pintype "bidirectional"))
    )
    (net (code "20") (name "MOSI") (class "Default")
      (node (ref "D2") (pin "2") (pinfunction "2_2") (pintype "passive"))
      (node (ref "J1") (pin "P3") (pinfunction "CMD_P3") (pintype "bidirectional"))
      (node (ref "J3") (pin "14") (pinfunction "14_14") (pintype "bidirectional"))
      (node (ref "R3") (pin "1") (pinfunction "1_1") (pintype "passive"))
      (node (ref "TP7") (pin "TP") (pinfunction "TP_TP") (pintype "input"))
      (node (ref "U1") (pin "7") (pinfunction "IO7_7") (pintype "bidirectional"))
      (node (ref "U3") (pin "5") (pinfunction "DI(IO0)_5") (pintype "bidirectional"))
    )
    (net (code "21") (name "Net-(CHG_LED-PadC)") (class "Default")
      (node (ref "CHG_LED") (pin "C") (pinfunction "C_C") (pintype "passive"))
      (node (ref "R1_BAT") (pin "2") (pinfunction "2_2") (pintype "passive"))
    )
    (net (code "22") (name "Net-(D7-CATHODE)") (class "Default")
      (node (ref "D7") (pin "1") (pinfunction "CATHODE_1") (pintype "bidirectional"))
      (node (ref "R_CAPACITOR") (pin "2") (pinfunction "2_2") (pintype "passive"))
    )
    (net (code "23") (name "Net-(D10-A)") (class "Default")
      (node (ref "C7") (pin "1") (pinfunction "1_1") (pintype "passive"))
      (node (ref "D10") (pin "2") (pinfunction "A_2") (pintype "bidirectional"))
      (node (ref "D9") (pin "1") (pinfunction "K_1") (pintype "bidirectional"))
    )
    (net (code "24") (name "Net-(DMG2305UX-7-S)") (class "Default")
      (node (ref "C1_BAT1") (pin "1") (pinfunction "1_1") (pintype "passive"))
      (node (ref "DMG2305UX-7") (pin "2") (pinfunction "S_2") (pintype "bidirectional"))
      (node (ref "IC1") (pin "1") (pinfunction "VIN_1") (pintype "bidirectional"))
      (node (ref "IC1") (pin "3") (pinfunction "CE_3") (pintype "bidirectional"))
      (node (ref "SD0805S020S1R0") (pin "1") (pinfunction "CATHODE_1") (pintype "bidirectional"))
    )
    (net (code "25") (name "Net-(EPD_C1-Pad1)") (class "Default")
      (node (ref "EPD_C1") (pin "1") (pinfunction "1_1") (pintype "passive"))
      (node (ref "J3") (pin "4") (pinfunction "4_4") (pintype "bidirectional"))
    )
    (net (code "26") (name "Net-(EPD_C2-Pad1)") (class "Default")
      (node (ref "EPD_C2") (pin "1") (pinfunction "1_1") (pintype "passive"))
      (node (ref "J3") (pin "5") (pinfunction "5_5") (pintype "bidirectional"))
    )
    (net (code "27") (name "Net-(EPD_C6-Pad1)") (class "Default")
      (node (ref "EPD_C6") (pin "1") (pinfunction "1_1") (pintype "passive"))
      (node (ref "J3") (pin "18") (pinfunction "18_18") (pintype "bidirectional"))
    )
    (net (code "28") (name "Net-(EPD_C7-Pad1)") (class "Default")
      (node (ref "EPD_C7") (pin "1") (pinfunction "1_1") (pintype "passive"))
      (node (ref "J3") (pin "19") (pinfunction "19_19") (pintype "bidirectional"))
    )
    (net (code "29") (name "Net-(EPD_C8-Pad1)") (class "Default")
      (node (ref "EPD_C8") (pin "1") (pinfunction "1_1") (pintype "passive"))
      (node (ref "J3") (pin "20") (pinfunction "20_20") (pintype "bidirectional"))
    )
    (net (code "30") (name "Net-(EPD_C10-Pad1)") (class "Default")
      (node (ref "EPD_C10") (pin "1") (pinfunction "1_1") (pintype "passive"))
      (node (ref "J3") (pin "22") (pinfunction "22_22") (pintype "bidirectional"))
    )
    (net (code "31") (name "Net-(EPD_C12-Pad1)") (class "Default")
      (node (ref "EPD_C12") (pin "1") (pinfunction "1_1") (pintype "passive"))
      (node (ref "J3") (pin "24") (pinfunction "24_24") (pintype "bidirectional"))
    )
    (net (code "32") (name "Net-(IC2-CT)") (class "Default")
      (node (ref "C_DELAY") (pin "1") (pinfunction "1_1") (pintype "passive"))
      (node (ref "IC2") (pin "5") (pinfunction "CT_5") (pintype "bidirectional"))
    )
    (net (code "33") (name "Net-(J4-PadA5)") (class "Default")
      (node (ref "J4") (pin "A5") (pinfunction "A5_A5") (pintype "bidirectional"))
      (node (ref "R2-USB1") (pin "2") (pinfunction "2_2") (pintype "passive"))
    )
    (net (code "34") (name "Net-(J4-PadB5)") (class "Default")
      (node (ref "J4") (pin "B5") (pinfunction "B5_B5") (pintype "bidirectional"))
      (node (ref "R2-USB") (pin "1") (pinfunction "1_1") (pintype "passive"))
    )
    (net (code "35") (name "Net-(MCP73831-PROG)") (class "Default")
      (node (ref "MCP73831") (pin "5") (pinfunction "PROG_5") (pintype "input"))
      (node (ref "R2_BAT") (pin "2") (pinfunction "2_2") (pintype "passive"))
    )
    (net (code "36") (name "Net-(MCP73831-STAT)") (class "Default")
      (node (ref "MCP73831") (pin "1") (pinfunction "STAT_1") (pintype "output"))
      (node (ref "R1_BAT") (pin "1") (pinfunction "1_1") (pintype "passive"))
    )
    (net (code "37") (name "PREVGH") (class "Default")
      (node (ref "D8") (pin "1") (pinfunction "K_1") (pintype "bidirectional"))
      (node (ref "EPD_C9") (pin "1") (pinfunction "1_1") (pintype "passive"))
      (node (ref "J3") (pin "21") (pinfunction "21_21") (pintype "bidirectional"))
    )
    (net (code "38") (name "PREVGL") (class "Default")
      (node (ref "D9") (pin "2") (pinfunction "A_2") (pintype "bidirectional"))
      (node (ref "EPD_C11") (pin "1") (pinfunction "1_1") (pintype "passive"))
      (node (ref "J3") (pin "23") (pinfunction "23_23") (pintype "bidirectional"))
    )
    (net (code "39") (name "RESE") (class "Default")
      (node (ref "J3") (pin "3") (pinfunction "3_3") (pintype "bidirectional"))
      (node (ref "Q2") (pin "2") (pinfunction "S_2") (pintype "bidirectional"))
      (node (ref "R10") (pin "1") (pinfunction "1_1") (pintype "passive"))
    )
    (net (code "40") (name "RESE'") (class "Default")
      (node (ref "R10") (pin "2") (pinfunction "2_2") (pintype "passive"))
      (node (ref "R8") (pin "2") (pinfunction "2_2") (pintype "passive"))
      (node (ref "SJ1") (pin "2") (pinfunction "2_2") (pintype "passive"))
    )
    (net (code "41") (name "RESET") (class "Default")
      (node (ref "C2") (pin "1") (pinfunction "1_1") (pintype "passive"))
      (node (ref "IC2") (pin "1") (pinfunction "VOUT_1") (pintype "bidirectional"))
      (node (ref "RESET_BUTTON") (pin "3") (pinfunction "3_3") (pintype "passive"))
      (node (ref "RESET_BUTTON") (pin "4") (pinfunction "4_4") (pintype "passive"))
      (node (ref "R_RESET") (pin "2") (pinfunction "2_2") (pintype "passive"))
      (node (ref "U1") (pin "3") (pinfunction "EN_3") (pintype "input"))
    )
    (net (code "42") (name "RTC_RST") (class "Default")
      (node (ref "U1") (pin "16") (pinfunction "IO18_16") (pintype "bidirectional"))
      (node (ref "U4") (pin "4") (pinfunction "~{RST}_4") (pintype "input"))
    )
    (net (code "43") (name "RX") (class "Default")
      (node (ref "TP2") (pin "TP") (pinfunction "TP_TP") (pintype "input"))
      (node (ref "U1") (pin "24") (pinfunction "RXD0/GPIO17_24") (pintype "bidirectional"))
    )
    (net (code "44") (name "SCK") (class "Default")
      (node (ref "D3") (pin "2") (pinfunction "2_2") (pintype "passive"))
      (node (ref "J1") (pin "P5") (pinfunction "CLK_P5") (pintype "bidirectional"))
      (node (ref "J3") (pin "13") (pinfunction "13_13") (pintype "bidirectional"))
      (node (ref "R4") (pin "1") (pinfunction "1_1") (pintype "passive"))
      (node (ref "TP8") (pin "TP") (pinfunction "TP_TP") (pintype "input"))
      (node (ref "U1") (pin "6") (pinfunction "IO6_6") (pintype "bidirectional"))
      (node (ref "U3") (pin "6") (pinfunction "CLK_6") (pintype "input"))
    )
    (net (code "45") (name "SCL") (class "Default")
      (node (ref "J2") (pin "4") (pinfunction "4_4") (pintype "passive"))
      (node (ref "R2-PINH") (pin "1") (pinfunction "1_1") (pintype "passive"))
      (node (ref "SENSOR2") (pin "4") (pinfunction "SCK_4") (pintype "input"))
      (node (ref "U1") (pin "20") (pinfunction "IO22_20") (pintype "bidirectional"))
      (node (ref "U2") (pin "7") (pinfunction "SCL_7") (pintype "input"))
      (node (ref "U4") (pin "16") (pinfunction "SCL_16") (pintype "input"))
    )
    (net (code "46") (name "SDA") (class "Default")
      (node (ref "J2") (pin "3") (pinfunction "3_3") (pintype "passive"))
      (node (ref "R1_PINH") (pin "1") (pinfunction "1_1") (pintype "passive"))
      (node (ref "SENSOR2") (pin "3") (pinfunction "SDI_3") (pintype "bidirectional"))
      (node (ref "U1") (pin "19") (pinfunction "IO21_19") (pintype "bidirectional"))
      (node (ref "U2") (pin "8") (pinfunction "SDA_8") (pintype "bidirectional"))
      (node (ref "U4") (pin "15") (pinfunction "SDA_15") (pintype "bidirectional"))
    )
    (net (code "47") (name "SRC") (class "Default")
      (node (ref "C7") (pin "2") (pinfunction "2_2") (pintype "passive"))
      (node (ref "D8") (pin "2") (pinfunction "A_2") (pintype "bidirectional"))
      (node (ref "L1") (pin "1") (pinfunction "1_1") (pintype "passive"))
      (node (ref "Q2") (pin "3") (pinfunction "D_3") (pintype "bidirectional"))
    )
    (net (code "48") (name "SS_SD") (class "Default")
      (node (ref "D6") (pin "2") (pinfunction "2_2") (pintype "passive"))
      (node (ref "J1") (pin "P2") (pinfunction "CD/DAT3_P2") (pintype "bidirectional"))
      (node (ref "R7") (pin "1") (pinfunction "1_1") (pintype "passive"))
      (node (ref "U1") (pin "4") (pinfunction "IO4_4") (pintype "bidirectional"))
    )
    (net (code "49") (name "TX") (class "Default")
      (node (ref "TP1") (pin "TP") (pinfunction "TP_TP") (pintype "input"))
      (node (ref "U1") (pin "25") (pinfunction "TXD0/GPIO16_25") (pintype "bidirectional"))
    )
    (net (code "50") (name "USB_D+") (class "Default")
      (node (ref "D11") (pin "1") (pinfunction "I/O1_1_1") (pintype "bidirectional"))
      (node (ref "U1") (pin "14") (pinfunction "IO13_14") (pintype "bidirectional"))
    )
    (net (code "51") (name "USB_D-") (class "Default")
      (node (ref "D11") (pin "3") (pinfunction "I/O2_1_3") (pintype "bidirectional"))
      (node (ref "U1") (pin "13") (pinfunction "IO12_13") (pintype "bidirectional"))
    )
    (net (code "52") (name "VBAT") (class "Default")
      (node (ref "C2_BAT") (pin "1") (pinfunction "1_1") (pintype "passive"))
      (node (ref "DMG2305UX-7") (pin "3") (pinfunction "D_3") (pintype "bidirectional"))
      (node (ref "MCP73831") (pin "3") (pinfunction "VBAT_3") (pintype "power_in"))
      (node (ref "TP3") (pin "TP") (pinfunction "TP_TP") (pintype "input"))
      (node (ref "U2") (pin "2") (pinfunction "CELL_2") (pintype "power_in"))
      (node (ref "U2") (pin "3") (pinfunction "VDD_3") (pintype "power_in"))
    )
    (net (code "53") (name "VBUS") (class "Default")
      (node (ref "C1_BAT") (pin "1") (pinfunction "1_1") (pintype "passive"))
      (node (ref "C4_USB") (pin "1") (pinfunction "1_1") (pintype "passive"))
      (node (ref "C5_USB") (pin "1") (pinfunction "1_1") (pintype "passive"))
      (node (ref "CHG_LED") (pin "A") (pinfunction "A_A") (pintype "passive"))
      (node (ref "D11") (pin "5") (pinfunction "VBUS_5") (pintype "bidirectional"))
      (node (ref "DMG2305UX-7") (pin "1") (pinfunction "G_1") (pintype "bidirectional"))
      (node (ref "MCP73831") (pin "4") (pinfunction "VIN_4") (pintype "power_in"))
      (node (ref "PFMF.050.1") (pin "2") (pinfunction "2_2") (pintype "passive"))
      (node (ref "R1_PWRUSB") (pin "2") (pinfunction "2_2") (pintype "passive"))
      (node (ref "SD0805S020S1R0") (pin "2") (pinfunction "ANODE_2") (pintype "bidirectional"))
      (node (ref "TP14") (pin "TP") (pinfunction "TP_TP") (pintype "input"))
    )
    (net (code "54") (name "VRTC") (class "Default")
      (node (ref "C10_SUPERCAP") (pin "2") (pinfunction "2_2") (pintype "passive"))
      (node (ref "C6") (pin "1") (pinfunction "1_1") (pintype "passive"))
      (node (ref "R_CAPACITOR") (pin "1") (pinfunction "1_1") (pintype "passive"))
      (node (ref "U4") (pin "14") (pinfunction "VBAT_14") (pintype "power_in"))
    )
    (net (code "55") (name "VUSB") (class "Default")
      (node (ref "J4") (pin "A4") (pinfunction "A4_A4") (pintype "bidirectional"))
      (node (ref "J4") (pin "A9") (pinfunction "A9_A9") (pintype "bidirectional"))
      (node (ref "J4") (pin "B4") (pinfunction "B4_B4") (pintype "bidirectional"))
      (node (ref "J4") (pin "B9") (pinfunction "B9_B9") (pintype "bidirectional"))
      (node (ref "PFMF.050.1") (pin "1") (pinfunction "1_1") (pintype "passive"))
    )
    (net (code "56") (name "unconnected-(IC1-NC-Pad4)") (class "Default")
      (node (ref "IC1") (pin "4") (pinfunction "NC_4") (pintype "no_connect"))
    )
    (net (code "57") (name "unconnected-(IC2-NC-Pad4)") (class "Default")
      (node (ref "IC2") (pin "4") (pinfunction "NC_4") (pintype "no_connect"))
    )
    (net (code "58") (name "unconnected-(J1-DAT1-PadP8)") (class "Default")
      (node (ref "J1") (pin "P8") (pinfunction "DAT1_P8") (pintype "bidirectional"))
    )
    (net (code "59") (name "unconnected-(J1-DAT2-PadP1)") (class "Default")
      (node (ref "J1") (pin "P1") (pinfunction "DAT2_P1") (pintype "bidirectional"))
    )
    (net (code "60") (name "unconnected-(J1-DETECTION_1-PadS1)") (class "Default")
      (node (ref "J1") (pin "S1") (pinfunction "DETECTION_1_S1") (pintype "bidirectional"))
    )
    (net (code "61") (name "unconnected-(J1-DETECTION_2-PadS2)") (class "Default")
      (node (ref "J1") (pin "S2") (pinfunction "DETECTION_2_S2") (pintype "bidirectional"))
    )
    (net (code "62") (name "unconnected-(J3-Pad1)") (class "Default")
      (node (ref "J3") (pin "1") (pinfunction "1_1") (pintype "bidirectional"))
    )
    (net (code "63") (name "unconnected-(J3-Pad6)") (class "Default")
      (node (ref "J3") (pin "6") (pinfunction "6_6") (pintype "bidirectional"))
    )
    (net (code "64") (name "unconnected-(J3-Pad7)") (class "Default")
      (node (ref "J3") (pin "7") (pinfunction "7_7") (pintype "bidirectional"))
    )
    (net (code "65") (name "unconnected-(J4-PadA8)") (class "Default")
      (node (ref "J4") (pin "A8") (pinfunction "A8_A8") (pintype "bidirectional"))
    )
    (net (code "66") (name "unconnected-(J4-PadB8)") (class "Default")
      (node (ref "J4") (pin "B8") (pinfunction "B8_B8") (pintype "bidirectional"))
    )
    (net (code "67") (name "unconnected-(U1-NC-Pad22)") (class "Default")
      (node (ref "U1") (pin "22") (pinfunction "NC_22") (pintype "no_connect"))
    )
    (net (code "68") (name "unconnected-(U2-~{ALERT}-Pad5)") (class "Default")
      (node (ref "U2") (pin "5") (pinfunction "~{ALERT}_5") (pintype "output"))
    )
  )
)
